# Rectifier.net
KiCad netlist of a schematic drawn in Altium Designer
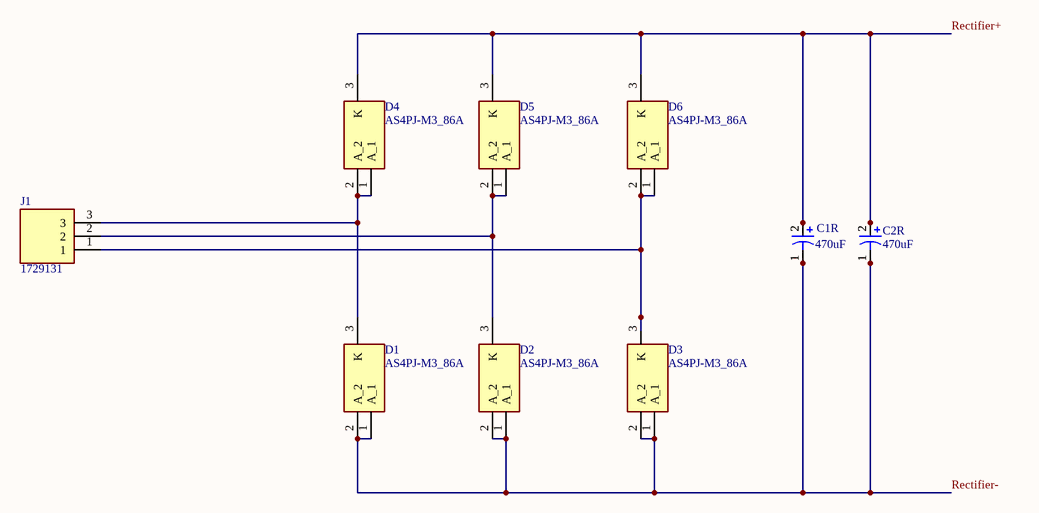
[diagram p0: Rectifier.SchDoc]

(export (version "E")
  (design (tool "Eeschema 10.0.6"))
  (components
    (comp (ref "C1R")
      (value "470uF")
      (footprint "450MXH270MEFCSN30X30")
      (libsource (lib "Schlib1") (part "450MXH270MEFCSN30X30"))
    )
    (comp (ref "C2R")
      (value "470uF")
      (footprint "450MXH270MEFCSN30X30")
      (libsource (lib "Schlib1") (part "450MXH270MEFCSN30X30"))
    )
    (comp (ref "D1")
      (value "AS4PJ-M3_86A")
      (footprint "SamacSys:V10PN50M387A")
      (description "Diode")
      (fields
        (field (name "MANUFACTURER_PART_NUMBER") "AS4PJ-M3/86A")
        (field (name "MOUSER PART NUMBER") "625-AS4PJ-M3/86A")
      )
      (libsource (lib "*") (part "AS4PJ-M3_86A"))
    )
    (comp (ref "D2")
      (value "AS4PJ-M3_86A")
      (footprint "SamacSys:V10PN50M387A")
      (description "Diode")
      (fields
        (field (name "MANUFACTURER_PART_NUMBER") "AS4PJ-M3/86A")
        (field (name "MOUSER PART NUMBER") "625-AS4PJ-M3/86A")
      )
      (libsource (lib "*") (part "AS4PJ-M3_86A"))
    )
    (comp (ref "D3")
      (value "AS4PJ-M3_86A")
      (footprint "SamacSys:V10PN50M387A")
      (description "Diode")
      (fields
        (field (name "MANUFACTURER_PART_NUMBER") "AS4PJ-M3/86A")
        (field (name "MOUSER PART NUMBER") "625-AS4PJ-M3/86A")
      )
      (libsource (lib "*") (part "AS4PJ-M3_86A"))
    )
    (comp (ref "D4")
      (value "AS4PJ-M3_86A")
      (footprint "SamacSys:V10PN50M387A")
      (description "Diode")
      (fields
        (field (name "MANUFACTURER_PART_NUMBER") "AS4PJ-M3/86A")
        (field (name "MOUSER PART NUMBER") "625-AS4PJ-M3/86A")
      )
      (libsource (lib "*") (part "AS4PJ-M3_86A"))
    )
    (comp (ref "D5")
      (value "AS4PJ-M3_86A")
      (footprint "SamacSys:V10PN50M387A")
      (description "Diode")
      (fields
        (field (name "MANUFACTURER_PART_NUMBER") "AS4PJ-M3/86A")
        (field (name "MOUSER PART NUMBER") "625-AS4PJ-M3/86A")
      )
      (libsource (lib "*") (part "AS4PJ-M3_86A"))
    )
    (comp (ref "D6")
      (value "AS4PJ-M3_86A")
      (footprint "SamacSys:V10PN50M387A")
      (description "Diode")
      (fields
        (field (name "MANUFACTURER_PART_NUMBER") "AS4PJ-M3/86A")
        (field (name "MOUSER PART NUMBER") "625-AS4PJ-M3/86A")
      )
      (libsource (lib "*") (part "AS4PJ-M3_86A"))
    )
    (comp (ref "J1")
      (value "1729131")
      (footprint "SamacSys:1729131")
      (description "Connector")
      (fields (field (name "MOUSER PART NUMBER") "651-1729131"))
      (libsource (lib "*") (part "1729131"))
    )
  )
  (nets
    (net (code "1") (name "/Rectifier+") (class "Default")
      (node (ref "C1R") (pin "2") (pinfunction "+_2") (pintype "passive"))
      (node (ref "C2R") (pin "2") (pinfunction "+_2") (pintype "passive"))
      (node (ref "D4") (pin "3") (pinfunction "K_3") (pintype "passive"))
      (node (ref "D5") (pin "3") (pinfunction "K_3") (pintype "passive"))
      (node (ref "D6") (pin "3") (pinfunction "K_3") (pintype "passive"))
    )
    (net (code "2") (name "/Rectifier-") (class "Default")
      (node (ref "C1R") (pin "1") (pinfunction "-_1") (pintype "passive"))
      (node (ref "C2R") (pin "1") (pinfunction "-_1") (pintype "passive"))
      (node (ref "D1") (pin "1") (pinfunction "A_1_1") (pintype "passive"))
      (node (ref "D1") (pin "2") (pinfunction "A_2_2") (pintype "passive"))
      (node (ref "D2") (pin "1") (pinfunction "A_1_1") (pintype "passive"))
      (node (ref "D2") (pin "2") (pinfunction "A_2_2") (pintype "passive"))
      (node (ref "D3") (pin "1") (pinfunction "A_1_1") (pintype "passive"))
      (node (ref "D3") (pin "2") (pinfunction "A_2_2") (pintype "passive"))
    )
    (net (code "3") (name "Net-(D1-K)") (class "Default")
      (node (ref "D1") (pin "3") (pinfunction "K_3") (pintype "passive"))
      (node (ref "D4") (pin "1") (pinfunction "A_1_1") (pintype "passive"))
      (node (ref "D4") (pin "2") (pinfunction "A_2_2") (pintype "passive"))
      (node (ref "J1") (pin "3") (pinfunction "3_3") (pintype "passive"))
    )
    (net (code "4") (name "Net-(D2-K)") (class "Default")
      (node (ref "D2") (pin "3") (pinfunction "K_3") (pintype "passive"))
      (node (ref "D5") (pin "1") (pinfunction "A_1_1") (pintype "passive"))
      (node (ref "D5") (pin "2") (pinfunction "A_2_2") (pintype "passive"))
      (node (ref "J1") (pin "2") (pinfunction "2_2") (pintype "passive"))
    )
    (net (code "5") (name "Net-(D3-K)") (class "Default")
      (node (ref "D3") (pin "3") (pinfunction "K_3") (pintype "passive"))
      (node (ref "D6") (pin "1") (pinfunction "A_1_1") (pintype "passive"))
      (node (ref "D6") (pin "2") (pinfunction "A_2_2") (pintype "passive"))
      (node (ref "J1") (pin "1") (pinfunction "1_1") (pintype "passive"))
    )
  )
)
